# MotorBoardDev.net
KiCad netlist of a schematic drawn in EAGLE
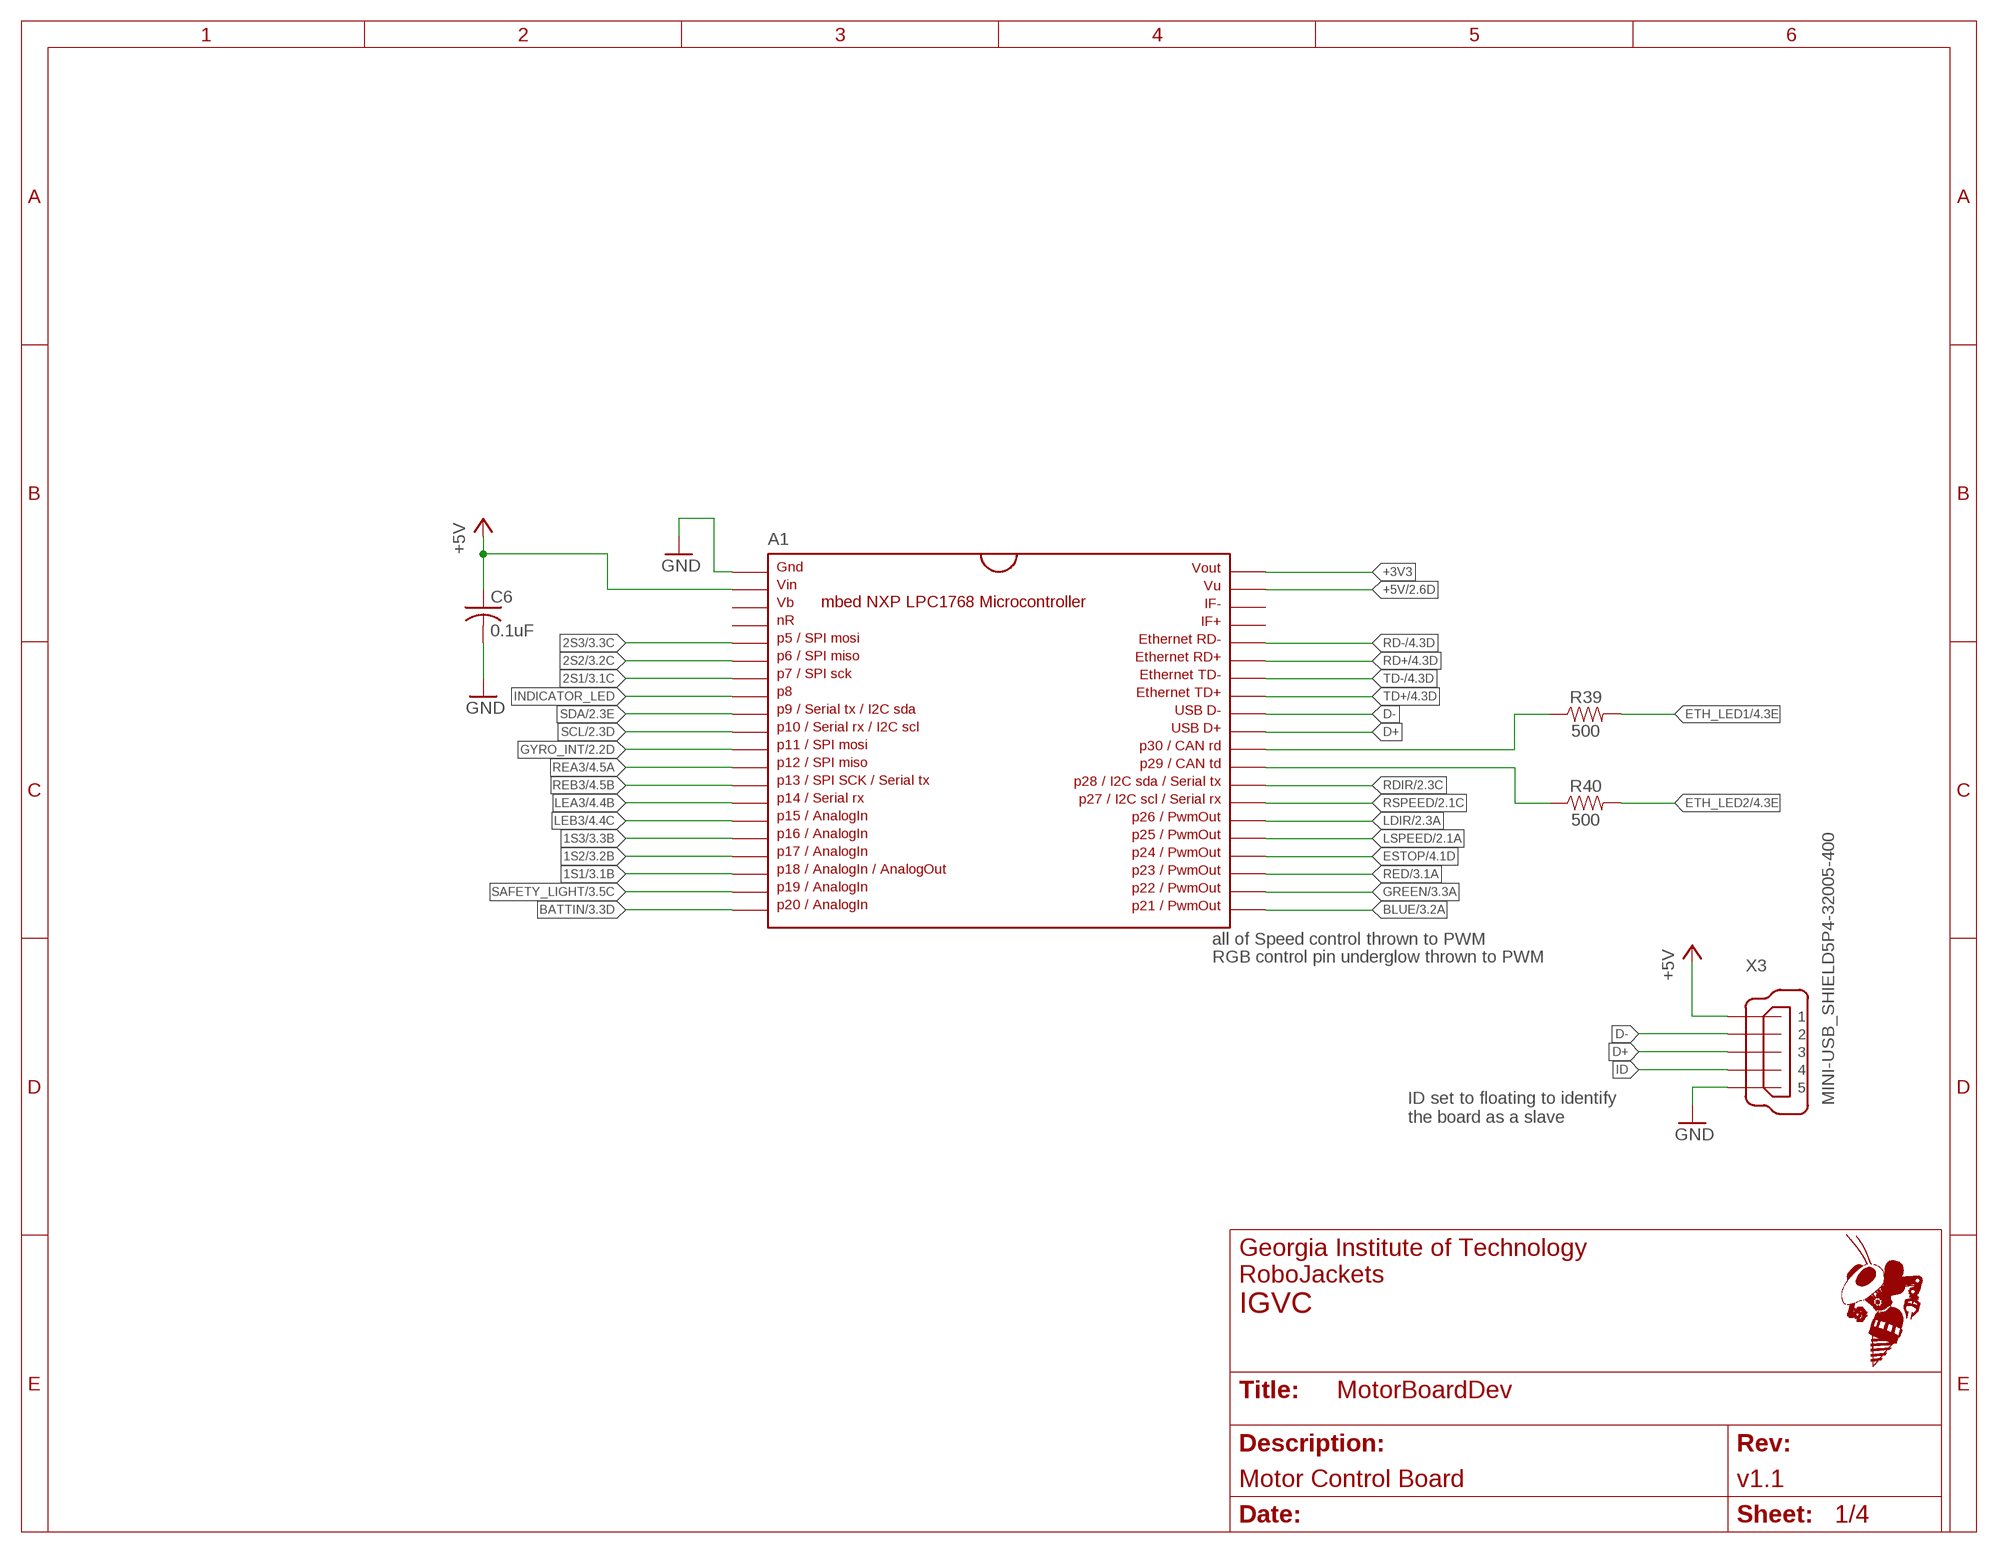
[diagram p0: schematic, sheet 1]
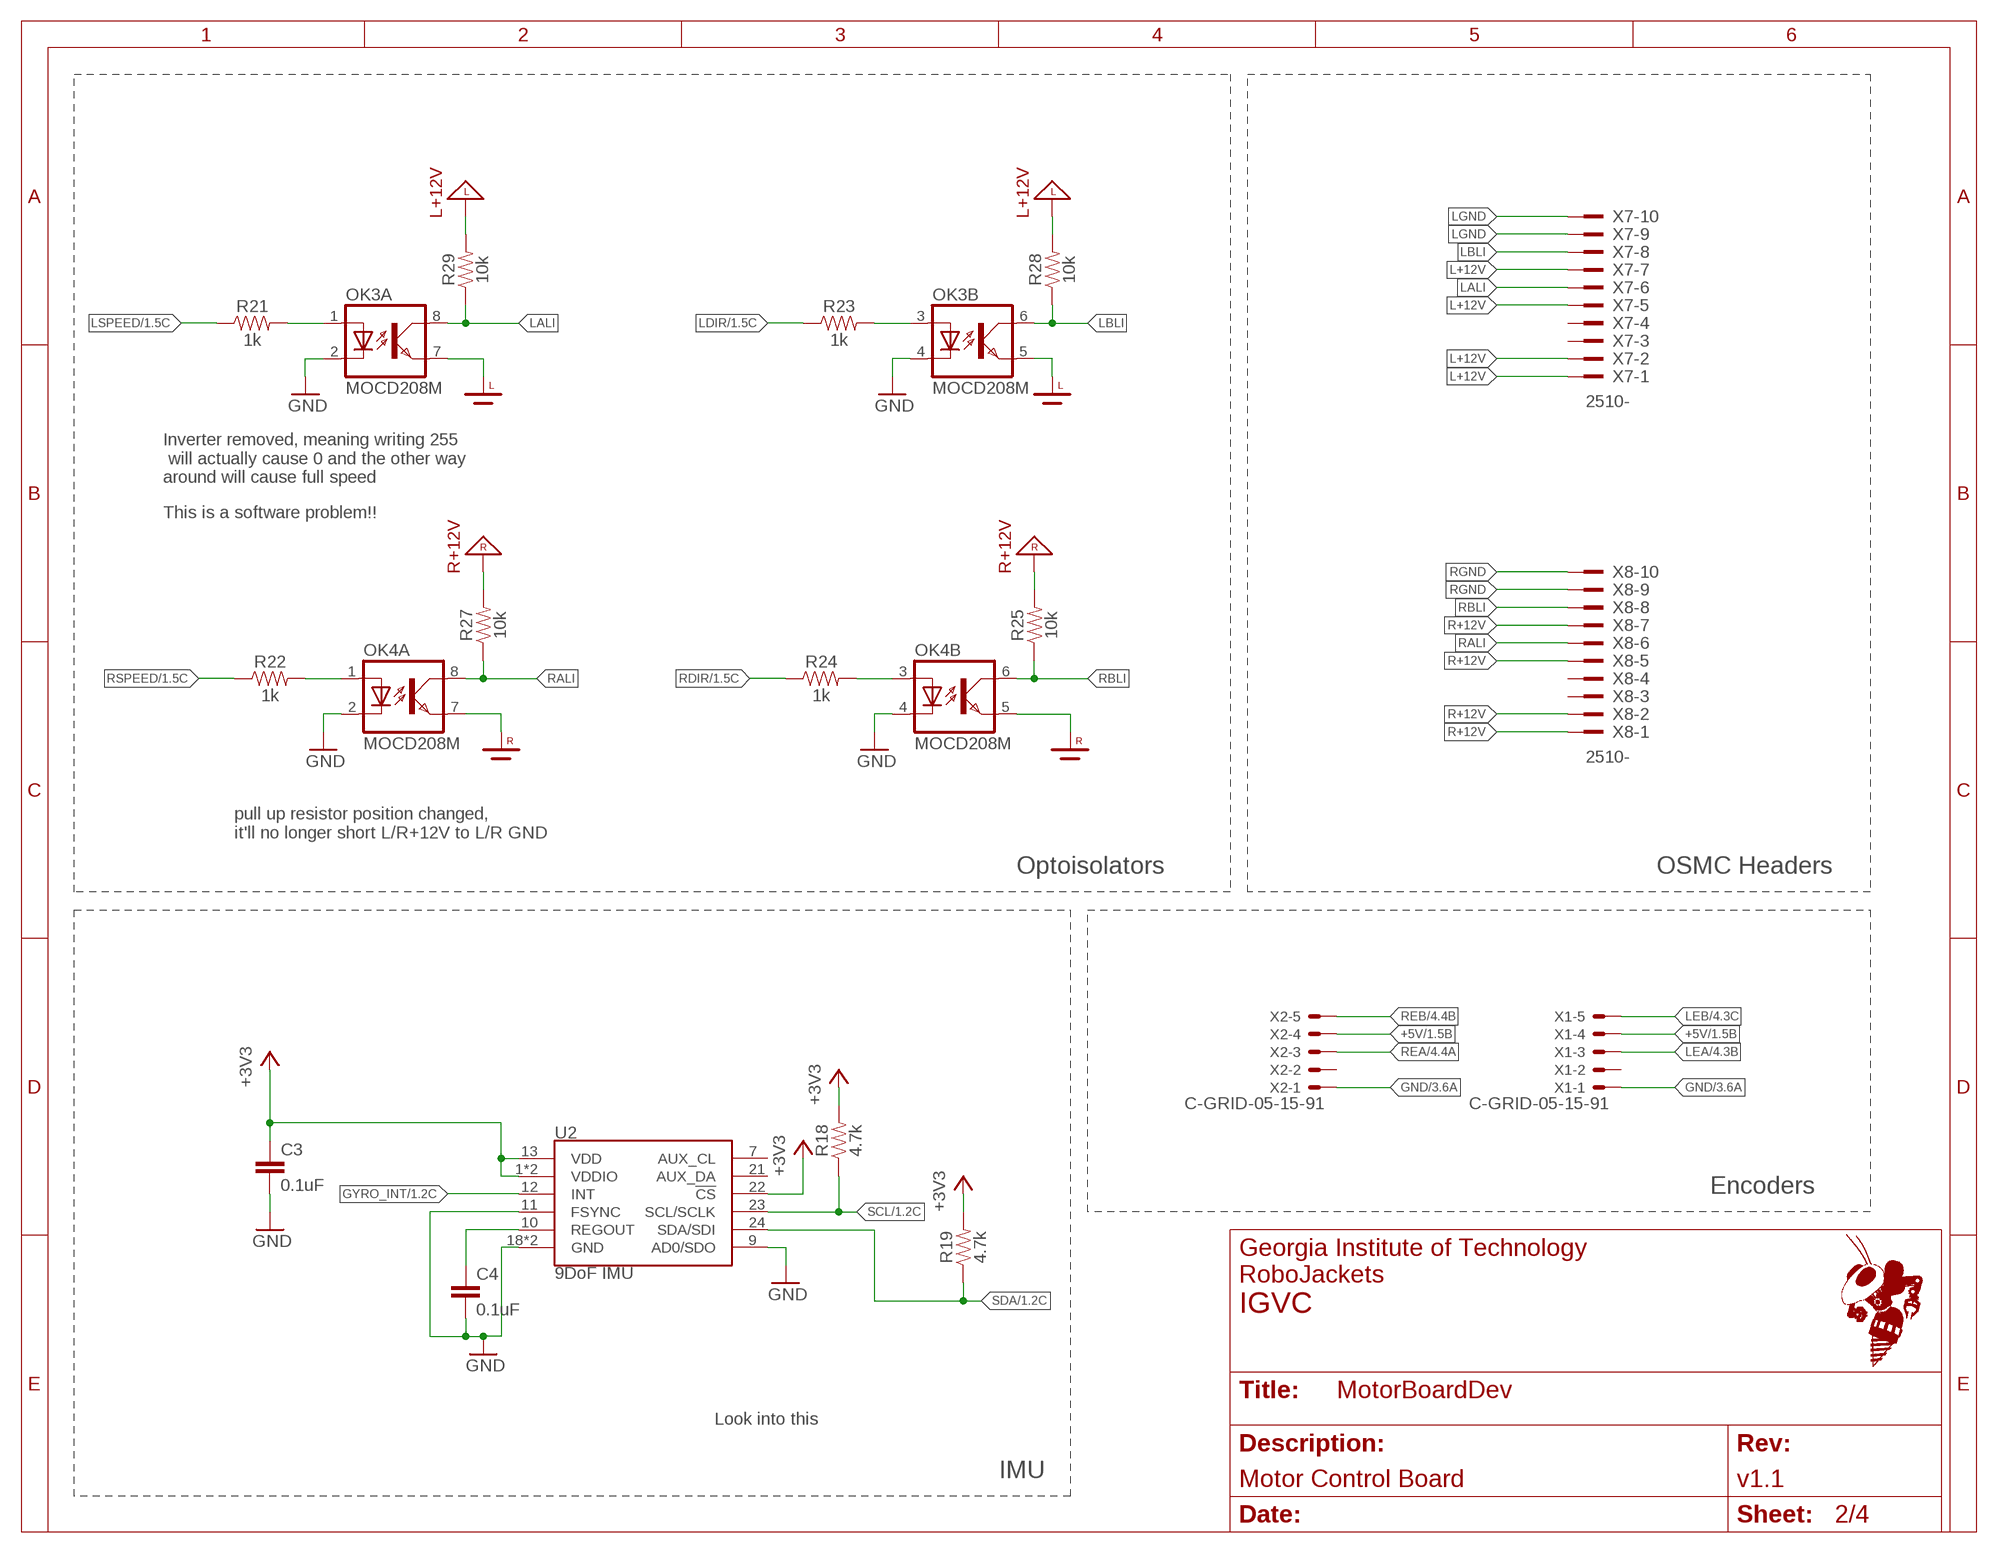
[diagram p1: schematic, sheet 2]
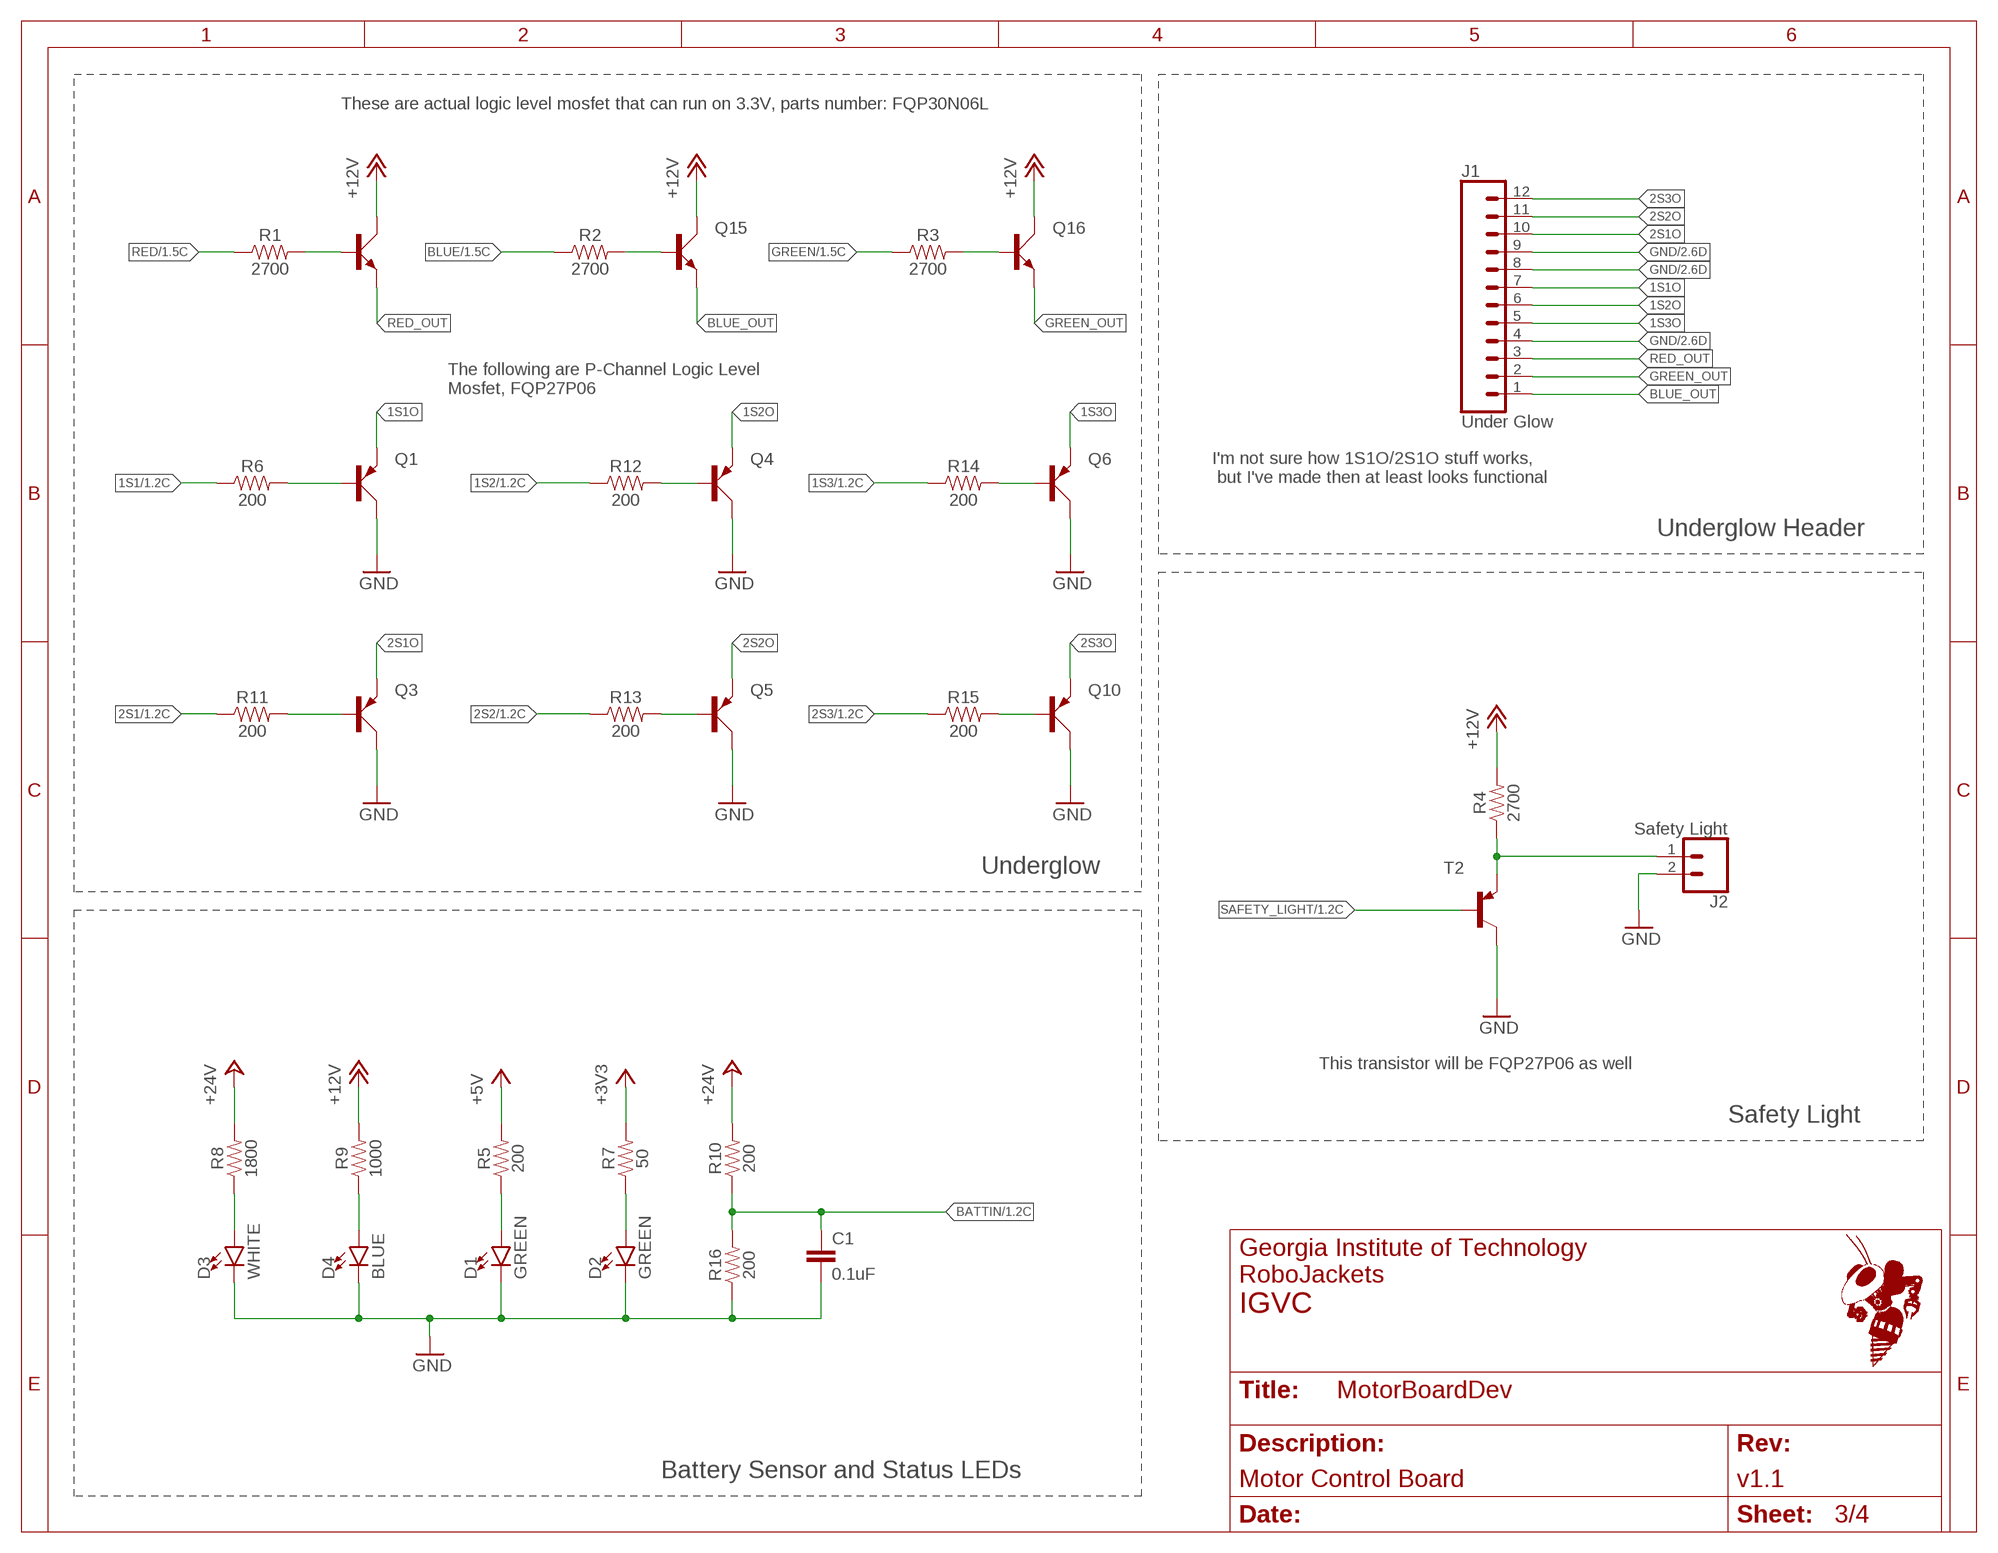
[diagram p2: schematic, sheet 3]
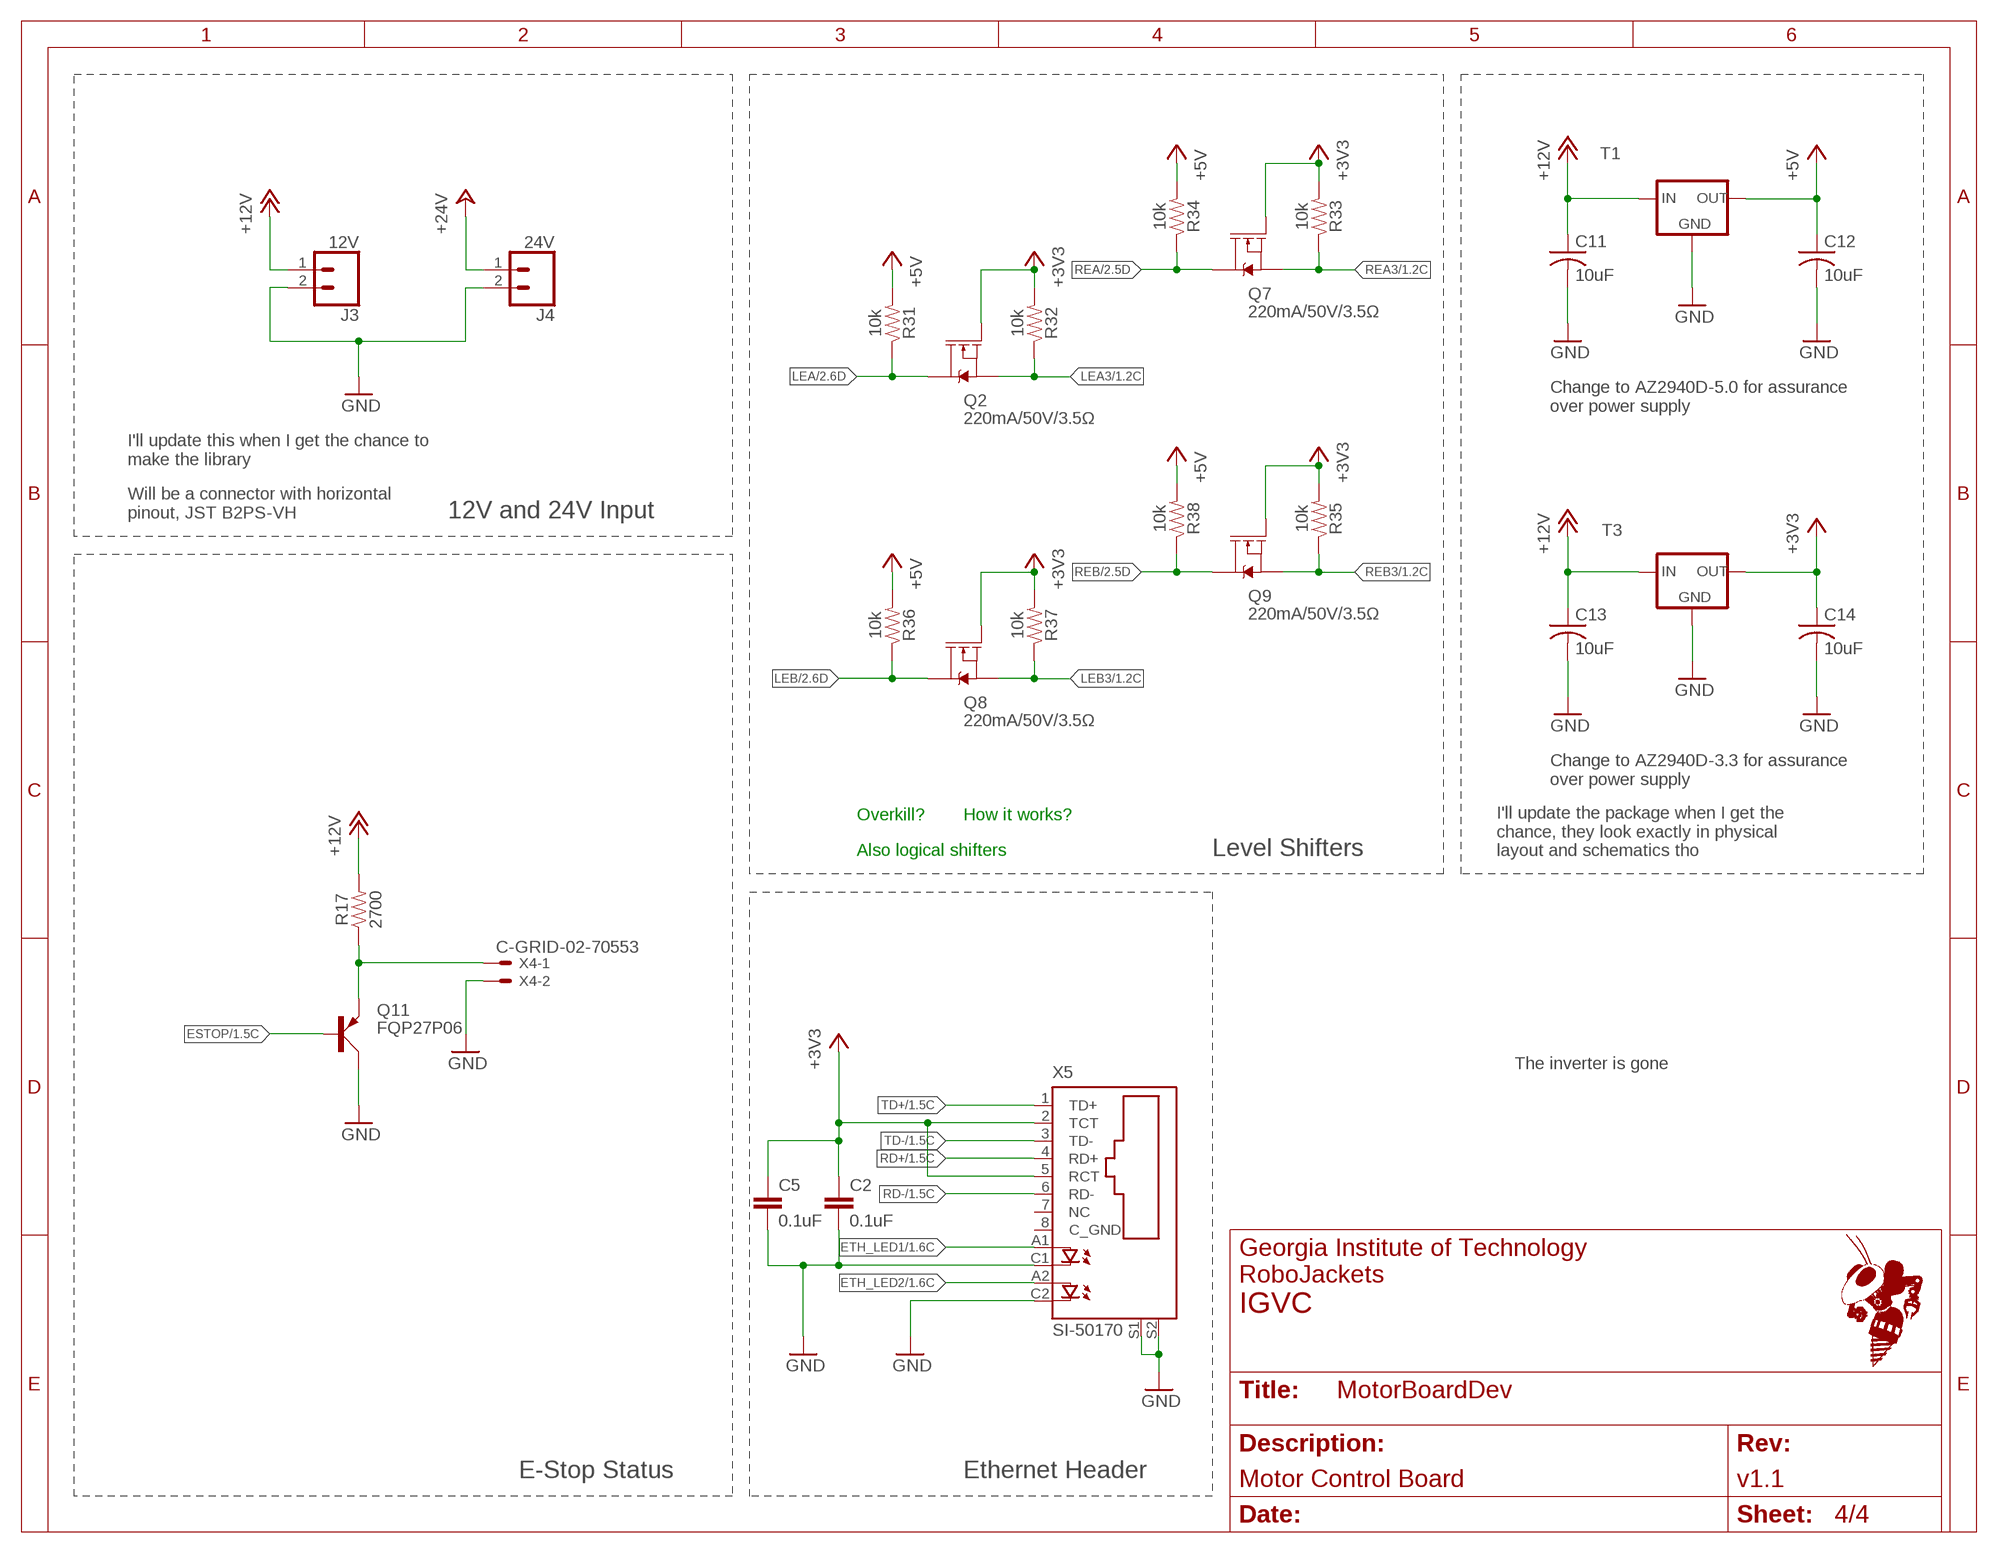
[diagram p3: schematic, sheet 4]

(export (version "E")
  (design (tool "Eeschema 10.0.6"))
  (components
    (comp (ref "C2")
      (value "0.1uF")
      (footprint "eagle-import:0603")
      (libsource (lib "eagle-import") (part "0.1UF-0603-25V-(+80/-20%)"))
    )
    (comp (ref "C5")
      (value "0.1uF")
      (footprint "eagle-import:0603")
      (libsource (lib "eagle-import") (part "0.1UF-0603-25V-(+80/-20%)"))
    )
    (comp (ref "C11")
      (value "10uF")
      (footprint "eagle-import:C0805")
      (libsource (lib "eagle-import") (part "C-USC0805"))
    )
    (comp (ref "C12")
      (value "10uF")
      (footprint "eagle-import:C0805")
      (libsource (lib "eagle-import") (part "C-USC0805"))
    )
    (comp (ref "C13")
      (value "10uF")
      (footprint "eagle-import:C0805")
      (libsource (lib "eagle-import") (part "C-USC0805"))
    )
    (comp (ref "C14")
      (value "10uF")
      (footprint "eagle-import:C0805")
      (libsource (lib "eagle-import") (part "C-USC0805"))
    )
    (comp (ref "J3")
      (value "12V")
      (footprint "eagle-import:SCREWTERMINAL-5MM-2")
      (libsource (lib "eagle-import") (part "CONN_025MM"))
    )
    (comp (ref "J4")
      (value "24V")
      (footprint "eagle-import:SCREWTERMINAL-5MM-2")
      (libsource (lib "eagle-import") (part "CONN_025MM"))
    )
    (comp (ref "Q2")
      (value "220mA/50V/3.5Ω")
      (footprint "eagle-import:SOT23-3")
      (libsource (lib "eagle-import") (part "MOSFET-NCH-BSS138"))
    )
    (comp (ref "Q7")
      (value "220mA/50V/3.5Ω")
      (footprint "eagle-import:SOT23-3")
      (libsource (lib "eagle-import") (part "MOSFET-NCH-BSS138"))
    )
    (comp (ref "Q8")
      (value "220mA/50V/3.5Ω")
      (footprint "eagle-import:SOT23-3")
      (libsource (lib "eagle-import") (part "MOSFET-NCH-BSS138"))
    )
    (comp (ref "Q9")
      (value "220mA/50V/3.5Ω")
      (footprint "eagle-import:SOT23-3")
      (libsource (lib "eagle-import") (part "MOSFET-NCH-BSS138"))
    )
    (comp (ref "Q11")
      (value "TIP42C")
      (footprint "eagle-import:TO220AV")
      (libsource (lib "eagle-import") (part "TIP42C"))
    )
    (comp (ref "R17")
      (value "2700")
      (footprint "eagle-import:0603")
      (libsource (lib "eagle-import") (part "3.9KOHM-0603-1/10W-1%"))
    )
    (comp (ref "R31")
      (value "10k")
      (footprint "eagle-import:0603")
      (libsource (lib "eagle-import") (part "10KOHM-0603-1/10W-1%"))
    )
    (comp (ref "R32")
      (value "10k")
      (footprint "eagle-import:0603")
      (libsource (lib "eagle-import") (part "10KOHM-0603-1/10W-1%"))
    )
    (comp (ref "R33")
      (value "10k")
      (footprint "eagle-import:0603")
      (libsource (lib "eagle-import") (part "10KOHM-0603-1/10W-1%"))
    )
    (comp (ref "R34")
      (value "10k")
      (footprint "eagle-import:0603")
      (libsource (lib "eagle-import") (part "10KOHM-0603-1/10W-1%"))
    )
    (comp (ref "R35")
      (value "10k")
      (footprint "eagle-import:0603")
      (libsource (lib "eagle-import") (part "10KOHM-0603-1/10W-1%"))
    )
    (comp (ref "R36")
      (value "10k")
      (footprint "eagle-import:0603")
      (libsource (lib "eagle-import") (part "10KOHM-0603-1/10W-1%"))
    )
    (comp (ref "R37")
      (value "10k")
      (footprint "eagle-import:0603")
      (libsource (lib "eagle-import") (part "10KOHM-0603-1/10W-1%"))
    )
    (comp (ref "R38")
      (value "10k")
      (footprint "eagle-import:0603")
      (libsource (lib "eagle-import") (part "10KOHM-0603-1/10W-1%"))
    )
    (comp (ref "T1")
      (value "NCP1117DT50GOS-ND")
      (footprint "eagle-import:TO252")
      (libsource (lib "eagle-import") (part "NCP1117DT50GOS-ND"))
    )
    (comp (ref "T3")
      (value "NCP1117DT33GOS-ND")
      (footprint "eagle-import:TO252")
      (libsource (lib "eagle-import") (part "NCP1117DT33GOS-ND"))
    )
    (comp (ref "X4")
      (value "C-GRID-02-70553")
      (footprint "eagle-import:70553-02")
      (libsource (lib "eagle-import") (part "C-GRID-02-70553"))
    )
    (comp (ref "X5")
      (value "SI-50170")
      (footprint "eagle-import:SI-50170")
      (libsource (lib "eagle-import") (part "SI-50170"))
    )
    (comp (ref "A1")
      (value "MBED1768")
      (footprint "eagle-import:SPARKFUN-BOARDS_DIL40_0.9")
      (libsource (lib "eagle-import") (part "SPARKFUN-BOARDS_MBED_NXP_LPC1768"))
    )
    (comp (ref "C6")
      (value "0.1uF")
      (footprint "eagle-import:C0603")
      (libsource (lib "eagle-import") (part "C-USC0603"))
    )
    (comp (ref "R39")
      (value "500")
      (footprint "eagle-import:0603")
      (libsource (lib "eagle-import") (part "1KOHM-0603-1/10W-1%"))
    )
    (comp (ref "R40")
      (value "500")
      (footprint "eagle-import:0603")
      (libsource (lib "eagle-import") (part "1KOHM-0603-1/10W-1%"))
    )
    (comp (ref "X3")
      (value "MINI-USB_SHIELD5P4-32005-400")
      (footprint "eagle-import:32005-400")
      (libsource (lib "eagle-import") (part "MINI-USB_SHIELD5P4-32005-400"))
    )
    (comp (ref "C1")
      (value "0.1uF")
      (footprint "eagle-import:0603")
      (libsource (lib "eagle-import") (part "SparkFun-Capacitors_510_0.1UF-0603-100V-10%"))
    )
    (comp (ref "D1")
      (value "GREEN")
      (footprint "eagle-import:LED-0603")
      (libsource (lib "eagle-import") (part "LED-GREEN0603"))
    )
    (comp (ref "D2")
      (value "GREEN")
      (footprint "eagle-import:LED-0603")
      (libsource (lib "eagle-import") (part "LED-GREEN0603"))
    )
    (comp (ref "D3")
      (value "WHITE")
      (footprint "eagle-import:LED-0603")
      (libsource (lib "eagle-import") (part "LED-WHITE0603"))
    )
    (comp (ref "D4")
      (value "BLUE")
      (footprint "eagle-import:LED-0603")
      (libsource (lib "eagle-import") (part "LED-BLUE0603"))
    )
    (comp (ref "FQP30N06L")
      (value "TIP41C")
      (footprint "eagle-import:TO220AV")
      (libsource (lib "eagle-import") (part "TIP41C"))
    )
    (comp (ref "J1")
      (value "Under Glow")
      (footprint "eagle-import:1X12_LOCK_LONGPADS")
      (libsource (lib "eagle-import") (part "CONN_12LOCK_LONGPADS"))
    )
    (comp (ref "J2")
      (value "Safety Light")
      (footprint "eagle-import:MOLEX-1X2")
      (libsource (lib "eagle-import") (part "SparkFun-Retired_CONN_02POLAR"))
    )
    (comp (ref "Q1")
      (value "TIP42C")
      (footprint "eagle-import:TO220AV")
      (libsource (lib "eagle-import") (part "TIP42C"))
    )
    (comp (ref "Q3")
      (value "TIP42C")
      (footprint "eagle-import:TO220AV")
      (libsource (lib "eagle-import") (part "TIP42C"))
    )
    (comp (ref "Q4")
      (value "TIP42C")
      (footprint "eagle-import:TO220AV")
      (libsource (lib "eagle-import") (part "TIP42C"))
    )
    (comp (ref "Q5")
      (value "TIP42C")
      (footprint "eagle-import:TO220AV")
      (libsource (lib "eagle-import") (part "TIP42C"))
    )
    (comp (ref "Q6")
      (value "TIP42C")
      (footprint "eagle-import:TO220AV")
      (libsource (lib "eagle-import") (part "TIP42C"))
    )
    (comp (ref "Q10")
      (value "TIP42C")
      (footprint "eagle-import:TO220AV")
      (libsource (lib "eagle-import") (part "TIP42C"))
    )
    (comp (ref "Q15")
      (value "TIP41C")
      (footprint "eagle-import:TO220AV")
      (libsource (lib "eagle-import") (part "TIP41C"))
    )
    (comp (ref "Q16")
      (value "TIP41C")
      (footprint "eagle-import:TO220AV")
      (libsource (lib "eagle-import") (part "TIP41C"))
    )
    (comp (ref "R1")
      (value "2700")
      (footprint "eagle-import:0603")
      (libsource (lib "eagle-import") (part "2.55KOHM-0603-1/10W-1%"))
    )
    (comp (ref "R2")
      (value "2700")
      (footprint "eagle-import:0603")
      (libsource (lib "eagle-import") (part "2.55KOHM-0603-1/10W-1%"))
    )
    (comp (ref "R3")
      (value "2700")
      (footprint "eagle-import:0603")
      (libsource (lib "eagle-import") (part "2.55KOHM-0603-1/10W-1%"))
    )
    (comp (ref "R4")
      (value "2700")
      (footprint "eagle-import:0603")
      (libsource (lib "eagle-import") (part "3.9KOHM-0603-1/10W-1%"))
    )
    (comp (ref "R5")
      (value "200")
      (footprint "eagle-import:0603")
      (libsource (lib "eagle-import") (part "200OHM-0603-1/10W-1%"))
    )
    (comp (ref "R6")
      (value "200")
      (footprint "eagle-import:0603")
      (libsource (lib "eagle-import") (part "200OHM-0603-1/10W-1%"))
    )
    (comp (ref "R7")
      (value "50")
      (footprint "eagle-import:0603")
      (libsource (lib "eagle-import") (part "200OHM-0603-1/10W-1%"))
    )
    (comp (ref "R8")
      (value "1800")
      (footprint "eagle-import:0603")
      (libsource (lib "eagle-import") (part "200OHM-0603-1/10W-1%"))
    )
    (comp (ref "R9")
      (value "1000")
      (footprint "eagle-import:0603")
      (libsource (lib "eagle-import") (part "200OHM-0603-1/10W-1%"))
    )
    (comp (ref "R10")
      (value "200")
      (footprint "eagle-import:0603")
      (libsource (lib "eagle-import") (part "200OHM-0603-1/10W-1%"))
    )
    (comp (ref "R11")
      (value "200")
      (footprint "eagle-import:0603")
      (libsource (lib "eagle-import") (part "200OHM-0603-1/10W-1%"))
    )
    (comp (ref "R12")
      (value "200")
      (footprint "eagle-import:0603")
      (libsource (lib "eagle-import") (part "200OHM-0603-1/10W-1%"))
    )
    (comp (ref "R13")
      (value "200")
      (footprint "eagle-import:0603")
      (libsource (lib "eagle-import") (part "200OHM-0603-1/10W-1%"))
    )
    (comp (ref "R14")
      (value "200")
      (footprint "eagle-import:0603")
      (libsource (lib "eagle-import") (part "200OHM-0603-1/10W-1%"))
    )
    (comp (ref "R15")
      (value "200")
      (footprint "eagle-import:0603")
      (libsource (lib "eagle-import") (part "200OHM-0603-1/10W-1%"))
    )
    (comp (ref "R16")
      (value "200")
      (footprint "eagle-import:0603")
      (libsource (lib "eagle-import") (part "200OHM-0603-1/10W-1%"))
    )
    (comp (ref "T2")
      (value "TIP41A")
      (footprint "eagle-import:TO220V")
      (libsource (lib "eagle-import") (part "-PNP-TO220V"))
    )
    (comp (ref "C3")
      (value "0.1uF")
      (footprint "eagle-import:0603")
      (libsource (lib "eagle-import") (part "0.1UF-0603-25V-(+80/-20%)"))
    )
    (comp (ref "C4")
      (value "0.1uF")
      (footprint "eagle-import:0603")
      (libsource (lib "eagle-import") (part "0.1UF-0603-25V-(+80/-20%)"))
    )
    (comp (ref "OK3")
      (value "MOCD208M")
      (footprint "eagle-import:SOIC08-FAIRCHILD")
      (fields (field (name "MF") "FAIRCHILD SEMICONDUCTOR"))
      (libsource (lib "eagle-import") (part "MOCD20M8"))
    )
    (comp (ref "OK4")
      (value "MOCD208M")
      (footprint "eagle-import:SOIC08-FAIRCHILD")
      (fields (field (name "MF") "FAIRCHILD SEMICONDUCTOR"))
      (libsource (lib "eagle-import") (part "MOCD20M8"))
    )
    (comp (ref "R18")
      (value "4.7k")
      (footprint "eagle-import:0603")
      (libsource (lib "eagle-import") (part "4.7KOHM-0603-1/10W-1%"))
    )
    (comp (ref "R19")
      (value "4.7k")
      (footprint "eagle-import:0603")
      (libsource (lib "eagle-import") (part "4.7KOHM-0603-1/10W-1%"))
    )
    (comp (ref "R21")
      (value "1k")
      (footprint "eagle-import:0603")
      (libsource (lib "eagle-import") (part "1KOHM-0603-1/10W-1%"))
    )
    (comp (ref "R22")
      (value "1k")
      (footprint "eagle-import:0603")
      (libsource (lib "eagle-import") (part "1KOHM-0603-1/10W-1%"))
    )
    (comp (ref "R23")
      (value "1k")
      (footprint "eagle-import:0603")
      (libsource (lib "eagle-import") (part "1KOHM-0603-1/10W-1%"))
    )
    (comp (ref "R24")
      (value "1k")
      (footprint "eagle-import:0603")
      (libsource (lib "eagle-import") (part "1KOHM-0603-1/10W-1%"))
    )
    (comp (ref "R25")
      (value "10k")
      (footprint "eagle-import:0603")
      (libsource (lib "eagle-import") (part "10KOHM-0603-1/10W-1%"))
    )
    (comp (ref "R27")
      (value "10k")
      (footprint "eagle-import:0603")
      (libsource (lib "eagle-import") (part "10KOHM-0603-1/10W-1%"))
    )
    (comp (ref "R28")
      (value "10k")
      (footprint "eagle-import:0603")
      (libsource (lib "eagle-import") (part "10KOHM-0603-1/10W-1%"))
    )
    (comp (ref "R29")
      (value "10k")
      (footprint "eagle-import:0603")
      (libsource (lib "eagle-import") (part "10KOHM-0603-1/10W-1%"))
    )
    (comp (ref "U2")
      (value "9DoF IMU")
      (footprint "eagle-import:QFN24-3X3")
      (libsource (lib "eagle-import") (part "MPU-9250"))
    )
    (comp (ref "X1")
      (value "C-GRID-05-15-91")
      (footprint "eagle-import:15-91-05")
      (libsource (lib "eagle-import") (part "C-GRID-05-15-91"))
    )
    (comp (ref "X2")
      (value "C-GRID-05-15-91")
      (footprint "eagle-import:15-91-05")
      (libsource (lib "eagle-import") (part "C-GRID-05-15-91"))
    )
    (comp (ref "X7")
      (value "2510-")
      (footprint "eagle-import:PAK100_2500-10")
      (fields (field (name "MF") "3M") (field (name "MPN") "2510-6002UB"))
      (libsource (lib "eagle-import") (part "2510-"))
    )
    (comp (ref "X8")
      (value "2510-")
      (footprint "eagle-import:PAK100_2500-10")
      (fields (field (name "MF") "3M") (field (name "MPN") "2510-6002UB"))
      (libsource (lib "eagle-import") (part "2510-"))
    )
  )
  (nets
    (net (code "1") (name "+3V3") (class "Default")
      (node (ref "A1") (pin "40") (pinfunction "P$40_40") (pintype "bidirectional"))
      (node (ref "C14") (pin "1") (pinfunction "1_1") (pintype "passive"))
      (node (ref "C2") (pin "1") (pinfunction "1_1") (pintype "passive"))
      (node (ref "C3") (pin "1") (pinfunction "1_1") (pintype "passive"))
      (node (ref "C5") (pin "1") (pinfunction "1_1") (pintype "passive"))
      (node (ref "Q2") (pin "1") (pinfunction "G_1") (pintype "bidirectional"))
      (node (ref "Q7") (pin "1") (pinfunction "G_1") (pintype "bidirectional"))
      (node (ref "Q8") (pin "1") (pinfunction "G_1") (pintype "bidirectional"))
      (node (ref "Q9") (pin "1") (pinfunction "G_1") (pintype "bidirectional"))
      (node (ref "R18") (pin "2") (pinfunction "2_2") (pintype "passive"))
      (node (ref "R19") (pin "2") (pinfunction "2_2") (pintype "passive"))
      (node (ref "R32") (pin "2") (pinfunction "2_2") (pintype "passive"))
      (node (ref "R33") (pin "2") (pinfunction "2_2") (pintype "passive"))
      (node (ref "R35") (pin "2") (pinfunction "2_2") (pintype "passive"))
      (node (ref "R37") (pin "2") (pinfunction "2_2") (pintype "passive"))
      (node (ref "R7") (pin "2") (pinfunction "2_2") (pintype "passive"))
      (node (ref "T3") (pin "2") (pinfunction "OUT_2") (pintype "passive"))
      (node (ref "U2") (pin "1") (pinfunction "VDDIO_1") (pintype "bidirectional"))
      (node (ref "U2") (pin "13") (pinfunction "VDD_13") (pintype "bidirectional"))
      (node (ref "U2") (pin "22") (pinfunction "~{CS}_22") (pintype "bidirectional"))
      (node (ref "U2") (pin "8") (pinfunction "VDDIO_8") (pintype "bidirectional"))
      (node (ref "X5") (pin "2") (pinfunction "TCT_2") (pintype "passive"))
      (node (ref "X5") (pin "5") (pinfunction "RCT_5") (pintype "passive"))
    )
    (net (code "2") (name "+5V") (class "Default")
      (node (ref "A1") (pin "2") (pinfunction "P$2_2") (pintype "bidirectional"))
      (node (ref "A1") (pin "39") (pinfunction "P$39_39") (pintype "bidirectional"))
      (node (ref "C12") (pin "1") (pinfunction "1_1") (pintype "passive"))
      (node (ref "C6") (pin "1") (pinfunction "1_1") (pintype "passive"))
      (node (ref "R31") (pin "2") (pinfunction "2_2") (pintype "passive"))
      (node (ref "R34") (pin "2") (pinfunction "2_2") (pintype "passive"))
      (node (ref "R36") (pin "2") (pinfunction "2_2") (pintype "passive"))
      (node (ref "R38") (pin "2") (pinfunction "2_2") (pintype "passive"))
      (node (ref "R5") (pin "2") (pinfunction "2_2") (pintype "passive"))
      (node (ref "T1") (pin "2") (pinfunction "OUT_2") (pintype "passive"))
      (node (ref "X1") (pin "4") (pinfunction "S_4") (pintype "passive"))
      (node (ref "X2") (pin "4") (pinfunction "S_4") (pintype "passive"))
      (node (ref "X3") (pin "1") (pinfunction "1_1") (pintype "passive"))
    )
    (net (code "3") (name "+12V") (class "Default")
      (node (ref "C11") (pin "1") (pinfunction "1_1") (pintype "passive"))
      (node (ref "C13") (pin "1") (pinfunction "1_1") (pintype "passive"))
      (node (ref "FQP30N06L") (pin "C") (pinfunction "C_C") (pintype "passive"))
      (node (ref "J3") (pin "1") (pinfunction "1_1") (pintype "passive"))
      (node (ref "Q15") (pin "C") (pinfunction "C_C") (pintype "passive"))
      (node (ref "Q16") (pin "C") (pinfunction "C_C") (pintype "passive"))
      (node (ref "R17") (pin "2") (pinfunction "2_2") (pintype "passive"))
      (node (ref "R4") (pin "2") (pinfunction "2_2") (pintype "passive"))
      (node (ref "R9") (pin "2") (pinfunction "2_2") (pintype "passive"))
      (node (ref "T1") (pin "3") (pinfunction "IN_3") (pintype "input"))
      (node (ref "T3") (pin "3") (pinfunction "IN_3") (pintype "input"))
    )
    (net (code "4") (name "+24V") (class "Default")
      (node (ref "J4") (pin "1") (pinfunction "1_1") (pintype "passive"))
      (node (ref "R10") (pin "2") (pinfunction "2_2") (pintype "passive"))
      (node (ref "R8") (pin "2") (pinfunction "2_2") (pintype "passive"))
    )
    (net (code "5") (name "1S1") (class "Default")
      (node (ref "A1") (pin "18") (pinfunction "P$18_18") (pintype "bidirectional"))
      (node (ref "R6") (pin "1") (pinfunction "1_1") (pintype "passive"))
    )
    (net (code "6") (name "1S1O") (class "Default")
      (node (ref "J1") (pin "7") (pinfunction "7_7") (pintype "passive"))
      (node (ref "Q1") (pin "E") (pinfunction "E_E") (pintype "passive"))
    )
    (net (code "7") (name "1S2") (class "Default")
      (node (ref "A1") (pin "17") (pinfunction "P$17_17") (pintype "bidirectional"))
      (node (ref "R12") (pin "1") (pinfunction "1_1") (pintype "passive"))
    )
    (net (code "8") (name "1S2O") (class "Default")
      (node (ref "J1") (pin "6") (pinfunction "6_6") (pintype "passive"))
      (node (ref "Q4") (pin "E") (pinfunction "E_E") (pintype "passive"))
    )
    (net (code "9") (name "1S3") (class "Default")
      (node (ref "A1") (pin "16") (pinfunction "P$16_16") (pintype "bidirectional"))
      (node (ref "R14") (pin "1") (pinfunction "1_1") (pintype "passive"))
    )
    (net (code "10") (name "1S3O") (class "Default")
      (node (ref "J1") (pin "5") (pinfunction "5_5") (pintype "passive"))
      (node (ref "Q6") (pin "E") (pinfunction "E_E") (pintype "passive"))
    )
    (net (code "11") (name "2S1") (class "Default")
      (node (ref "A1") (pin "7") (pinfunction "P$7_7") (pintype "bidirectional"))
      (node (ref "R11") (pin "1") (pinfunction "1_1") (pintype "passive"))
    )
    (net (code "12") (name "2S1O") (class "Default")
      (node (ref "J1") (pin "10") (pinfunction "10_10") (pintype "passive"))
      (node (ref "Q3") (pin "E") (pinfunction "E_E") (pintype "passive"))
    )
    (net (code "13") (name "2S2") (class "Default")
      (node (ref "A1") (pin "6") (pinfunction "P$6_6") (pintype "bidirectional"))
      (node (ref "R13") (pin "1") (pinfunction "1_1") (pintype "passive"))
    )
    (net (code "14") (name "2S2O") (class "Default")
      (node (ref "J1") (pin "11") (pinfunction "11_11") (pintype "passive"))
      (node (ref "Q5") (pin "E") (pinfunction "E_E") (pintype "passive"))
    )
    (net (code "15") (name "2S3") (class "Default")
      (node (ref "A1") (pin "5") (pinfunction "P$5_5") (pintype "bidirectional"))
      (node (ref "R15") (pin "1") (pinfunction "1_1") (pintype "passive"))
    )
    (net (code "16") (name "2S3O") (class "Default")
      (node (ref "J1") (pin "12") (pinfunction "12_12") (pintype "passive"))
      (node (ref "Q10") (pin "E") (pinfunction "E_E") (pintype "passive"))
    )
    (net (code "17") (name "BATTIN") (class "Default")
      (node (ref "A1") (pin "20") (pinfunction "P$20_20") (pintype "bidirectional"))
      (node (ref "C1") (pin "1") (pinfunction "1_1") (pintype "passive"))
      (node (ref "R10") (pin "1") (pinfunction "1_1") (pintype "passive"))
      (node (ref "R16") (pin "2") (pinfunction "2_2") (pintype "passive"))
    )
    (net (code "18") (name "BLUE") (class "Default")
      (node (ref "A1") (pin "21") (pinfunction "P$21_21") (pintype "bidirectional"))
      (node (ref "R2") (pin "1") (pinfunction "1_1") (pintype "passive"))
    )
    (net (code "19") (name "BLUE_OUT") (class "Default")
      (node (ref "J1") (pin "1") (pinfunction "1_1") (pintype "passive"))
      (node (ref "Q15") (pin "E") (pinfunction "E_E") (pintype "passive"))
    )
    (net (code "20") (name "D+") (class "Default")
      (node (ref "A1") (pin "31") (pinfunction "P$31_31") (pintype "bidirectional"))
      (node (ref "X3") (pin "3") (pinfunction "3_3") (pintype "passive"))
    )
    (net (code "21") (name "D-") (class "Default")
      (node (ref "A1") (pin "32") (pinfunction "P$32_32") (pintype "bidirectional"))
      (node (ref "X3") (pin "2") (pinfunction "2_2") (pintype "passive"))
    )
    (net (code "22") (name "ESTOP") (class "Default")
      (node (ref "A1") (pin "24") (pinfunction "P$24_24") (pintype "bidirectional"))
      (node (ref "Q11") (pin "B") (pinfunction "B_B") (pintype "passive"))
    )
    (net (code "23") (name "ETH_LED1") (class "Default")
      (node (ref "R39") (pin "2") (pinfunction "2_2") (pintype "passive"))
      (node (ref "X5") (pin "A1") (pinfunction "A_A1") (pintype "passive"))
    )
    (net (code "24") (name "ETH_LED2") (class "Default")
      (node (ref "R40") (pin "2") (pinfunction "2_2") (pintype "passive"))
      (node (ref "X5") (pin "A2") (pinfunction "A1_A2") (pintype "passive"))
    )
    (net (code "25") (name "GND") (class "Default")
      (node (ref "A1") (pin "1") (pinfunction "P$1_1") (pintype "bidirectional"))
      (node (ref "C1") (pin "2") (pinfunction "2_2") (pintype "passive"))
      (node (ref "C11") (pin "2") (pinfunction "2_2") (pintype "passive"))
      (node (ref "C12") (pin "2") (pinfunction "2_2") (pintype "passive"))
      (node (ref "C13") (pin "2") (pinfunction "2_2") (pintype "passive"))
      (node (ref "C14") (pin "2") (pinfunction "2_2") (pintype "passive"))
      (node (ref "C2") (pin "2") (pinfunction "2_2") (pintype "passive"))
      (node (ref "C3") (pin "2") (pinfunction "2_2") (pintype "passive"))
      (node (ref "C4") (pin "2") (pinfunction "2_2") (pintype "passive"))
      (node (ref "C5") (pin "2") (pinfunction "2_2") (pintype "passive"))
      (node (ref "C6") (pin "2") (pinfunction "2_2") (pintype "passive"))
      (node (ref "D1") (pin "C") (pinfunction "C_C") (pintype "passive"))
      (node (ref "D2") (pin "C") (pinfunction "C_C") (pintype "passive"))
      (node (ref "D3") (pin "C") (pinfunction "C_C") (pintype "passive"))
      (node (ref "D4") (pin "C") (pinfunction "C_C") (pintype "passive"))
      (node (ref "J1") (pin "4") (pinfunction "4_4") (pintype "passive"))
      (node (ref "J1") (pin "8") (pinfunction "8_8") (pintype "passive"))
      (node (ref "J1") (pin "9") (pinfunction "9_9") (pintype "passive"))
      (node (ref "J2") (pin "2") (pinfunction "2_2") (pintype "passive"))
      (node (ref "J3") (pin "2") (pinfunction "2_2") (pintype "passive"))
      (node (ref "J4") (pin "2") (pinfunction "2_2") (pintype "passive"))
      (node (ref "OK3") (pin "2") (pinfunction "C_2") (pintype "passive"))
      (node (ref "OK3") (pin "4") (pinfunction "C_4") (pintype "passive"))
      (node (ref "OK4") (pin "2") (pinfunction "C_2") (pintype "passive"))
      (node (ref "OK4") (pin "4") (pinfunction "C_4") (pintype "passive"))
      (node (ref "Q1") (pin "C") (pinfunction "C_C") (pintype "passive"))
      (node (ref "Q10") (pin "C") (pinfunction "C_C") (pintype "passive"))
      (node (ref "Q11") (pin "C") (pinfunction "C_C") (pintype "passive"))
      (node (ref "Q3") (pin "C") (pinfunction "C_C") (pintype "passive"))
      (node (ref "Q4") (pin "C") (pinfunction "C_C") (pintype "passive"))
      (node (ref "Q5") (pin "C") (pinfunction "C_C") (pintype "passive"))
      (node (ref "Q6") (pin "C") (pinfunction "C_C") (pintype "passive"))
      (node (ref "R16") (pin "1") (pinfunction "1_1") (pintype "passive"))
      (node (ref "T1") (pin "1") (pinfunction "GND_1") (pintype "input"))
      (node (ref "T2") (pin "2") (pinfunction "C_2") (pintype "passive"))
      (node (ref "T3") (pin "1") (pinfunction "GND_1") (pintype "input"))
      (node (ref "U2") (pin "11") (pinfunction "FSYNC_11") (pintype "bidirectional"))
      (node (ref "U2") (pin "18") (pinfunction "GND_18") (pintype "bidirectional"))
      (node (ref "U2") (pin "20") (pinfunction "GND_20") (pintype "bidirectional"))
      (node (ref "U2") (pin "9") (pinfunction "AD0/SDO_9") (pintype "bidirectional"))
      (node (ref "X1") (pin "1") (pinfunction "S_1") (pintype "passive"))
      (node (ref "X2") (pin "1") (pinfunction "S_1") (pintype "passive"))
      (node (ref "X3") (pin "5") (pinfunction "5_5") (pintype "passive"))
      (node (ref "X4") (pin "2") (pinfunction "S_2") (pintype "passive"))
      (node (ref "X5") (pin "C1") (pinfunction "C_C1") (pintype "passive"))
      (node (ref "X5") (pin "C2") (pinfunction "C1_C2") (pintype "passive"))
      (node (ref "X5") (pin "S1") (pinfunction "S1_S1") (pintype "passive"))
      (node (ref "X5") (pin "S2") (pinfunction "S2_S2") (pintype "passive"))
    )
    (net (code "26") (name "GREEN") (class "Default")
      (node (ref "A1") (pin "22") (pinfunction "P$22_22") (pintype "bidirectional"))
      (node (ref "R3") (pin "1") (pinfunction "1_1") (pintype "passive"))
    )
    (net (code "27") (name "GREEN_OUT") (class "Default")
      (node (ref "J1") (pin "2") (pinfunction "2_2") (pintype "passive"))
      (node (ref "Q16") (pin "E") (pinfunction "E_E") (pintype "passive"))
    )
    (net (code "28") (name "GYRO_INT") (class "Default")
      (node (ref "A1") (pin "11") (pinfunction "P$11_11") (pintype "bidirectional"))
      (node (ref "U2") (pin "12") (pinfunction "INT_12") (pintype "bidirectional"))
    )
    (net (code "29") (name "ID") (class "Default")
      (node (ref "X3") (pin "4") (pinfunction "4_4") (pintype "passive"))
    )
    (net (code "30") (name "INDICATOR_LED") (class "Default")
      (node (ref "A1") (pin "8") (pinfunction "P$8_8") (pintype "bidirectional"))
    )
    (net (code "31") (name "L+12V") (class "Default")
      (node (ref "R28") (pin "2") (pinfunction "2_2") (pintype "passive"))
      (node (ref "R29") (pin "2") (pinfunction "2_2") (pintype "passive"))
      (node (ref "X7") (pin "1") (pinfunction "KL_1") (pintype "passive"))
      (node (ref "X7") (pin "2") (pinfunction "KL_2") (pintype "passive"))
      (node (ref "X7") (pin "5") (pinfunction "KL_5") (pintype "passive"))
      (node (ref "X7") (pin "7") (pinfunction "KL_7") (pintype "passive"))
    )
    (net (code "32") (name "LALI") (class "Default")
      (node (ref "OK3") (pin "8") (pinfunction "COL_8") (pintype "passive"))
      (node (ref "R29") (pin "1") (pinfunction "1_1") (pintype "passive"))
      (node (ref "X7") (pin "6") (pinfunction "KL_6") (pintype "passive"))
    )
    (net (code "33") (name "LBLI") (class "Default")
      (node (ref "OK3") (pin "6") (pinfunction "COL_6") (pintype "passive"))
      (node (ref "R28") (pin "1") (pinfunction "1_1") (pintype "passive"))
      (node (ref "X7") (pin "8") (pinfunction "KL_8") (pintype "passive"))
    )
    (net (code "34") (name "LDIR") (class "Default")
      (node (ref "A1") (pin "26") (pinfunction "P$26_26") (pintype "bidirectional"))
      (node (ref "R23") (pin "1") (pinfunction "1_1") (pintype "passive"))
    )
    (net (code "35") (name "LEA") (class "Default")
      (node (ref "Q2") (pin "3") (pinfunction "D_3") (pintype "bidirectional"))
      (node (ref "R31") (pin "1") (pinfunction "1_1") (pintype "passive"))
      (node (ref "X1") (pin "3") (pinfunction "S_3") (pintype "passive"))
    )
    (net (code "36") (name "LEA3") (class "Default")
      (node (ref "A1") (pin "14") (pinfunction "P$14_14") (pintype "bidirectional"))
      (node (ref "Q2") (pin "2") (pinfunction "S_2") (pintype "bidirectional"))
      (node (ref "R32") (pin "1") (pinfunction "1_1") (pintype "passive"))
    )
    (net (code "37") (name "LEB") (class "Default")
      (node (ref "Q8") (pin "3") (pinfunction "D_3") (pintype "bidirectional"))
      (node (ref "R36") (pin "1") (pinfunction "1_1") (pintype "passive"))
      (node (ref "X1") (pin "5") (pinfunction "S_5") (pintype "passive"))
    )
    (net (code "38") (name "LEB3") (class "Default")
      (node (ref "A1") (pin "15") (pinfunction "P$15_15") (pintype "bidirectional"))
      (node (ref "Q8") (pin "2") (pinfunction "S_2") (pintype "bidirectional"))
      (node (ref "R37") (pin "1") (pinfunction "1_1") (pintype "passive"))
    )
    (net (code "39") (name "LGND") (class "Default")
      (node (ref "OK3") (pin "5") (pinfunction "EMIT_5") (pintype "passive"))
      (node (ref "OK3") (pin "7") (pinfunction "EMIT_7") (pintype "passive"))
      (node (ref "X7") (pin "10") (pinfunction "KL_10") (pintype "passive"))
      (node (ref "X7") (pin "9") (pinfunction "KL_9") (pintype "passive"))
    )
    (net (code "40") (name "LSPEED") (class "Default")
      (node (ref "A1") (pin "25") (pinfunction "P$25_25") (pintype "bidirectional"))
      (node (ref "R21") (pin "1") (pinfunction "1_1") (pintype "passive"))
    )
    (net (code "41") (name "Net-(A1-P$29)") (class "Default")
      (node (ref "A1") (pin "29") (pinfunction "P$29_29") (pintype "bidirectional"))
      (node (ref "R40") (pin "1") (pinfunction "1_1") (pintype "passive"))
    )
    (net (code "42") (name "Net-(A1-P$30)") (class "Default")
      (node (ref "A1") (pin "30") (pinfunction "P$30_30") (pintype "bidirectional"))
      (node (ref "R39") (pin "1") (pinfunction "1_1") (pintype "passive"))
    )
    (net (code "43") (name "Net-(D1-PadA)") (class "Default")
      (node (ref "D1") (pin "A") (pinfunction "A_A") (pintype "passive"))
      (node (ref "R5") (pin "1") (pinfunction "1_1") (pintype "passive"))
    )
    (net (code "44") (name "Net-(D2-PadA)") (class "Default")
      (node (ref "D2") (pin "A") (pinfunction "A_A") (pintype "passive"))
      (node (ref "R7") (pin "1") (pinfunction "1_1") (pintype "passive"))
    )
    (net (code "45") (name "Net-(D3-PadA)") (class "Default")
      (node (ref "D3") (pin "A") (pinfunction "A_A") (pintype "passive"))
      (node (ref "R8") (pin "1") (pinfunction "1_1") (pintype "passive"))
    )
    (net (code "46") (name "Net-(D4-PadA)") (class "Default")
      (node (ref "D4") (pin "A") (pinfunction "A_A") (pintype "passive"))
      (node (ref "R9") (pin "1") (pinfunction "1_1") (pintype "passive"))
    )
    (net (code "47") (name "Net-(FQP30N06L-PadB)") (class "Default")
      (node (ref "FQP30N06L") (pin "B") (pinfunction "B_B") (pintype "passive"))
      (node (ref "R1") (pin "2") (pinfunction "2_2") (pintype "passive"))
    )
    (net (code "48") (name "Net-(OK3A-A)") (class "Default")
      (node (ref "OK3") (pin "1") (pinfunction "A_1") (pintype "passive"))
      (node (ref "R21") (pin "2") (pinfunction "2_2") (pintype "passive"))
    )
    (net (code "49") (name "Net-(OK3B-A)") (class "Default")
      (node (ref "OK3") (pin "3") (pinfunction "A_3") (pintype "passive"))
      (node (ref "R23") (pin "2") (pinfunction "2_2") (pintype "passive"))
    )
    (net (code "50") (name "Net-(OK4A-A)") (class "Default")
      (node (ref "OK4") (pin "1") (pinfunction "A_1") (pintype "passive"))
      (node (ref "R22") (pin "2") (pinfunction "2_2") (pintype "passive"))
    )
    (net (code "51") (name "Net-(OK4B-A)") (class "Default")
      (node (ref "OK4") (pin "3") (pinfunction "A_3") (pintype "passive"))
      (node (ref "R24") (pin "2") (pinfunction "2_2") (pintype "passive"))
    )
    (net (code "52") (name "Net-(Q1-PadB)") (class "Default")
      (node (ref "Q1") (pin "B") (pinfunction "B_B") (pintype "passive"))
      (node (ref "R6") (pin "2") (pinfunction "2_2") (pintype "passive"))
    )
    (net (code "53") (name "Net-(Q3-PadB)") (class "Default")
      (node (ref "Q3") (pin "B") (pinfunction "B_B") (pintype "passive"))
      (node (ref "R11") (pin "2") (pinfunction "2_2") (pintype "passive"))
    )
    (net (code "54") (name "Net-(Q4-PadB)") (class "Default")
      (node (ref "Q4") (pin "B") (pinfunction "B_B") (pintype "passive"))
      (node (ref "R12") (pin "2") (pinfunction "2_2") (pintype "passive"))
    )
    (net (code "55") (name "Net-(Q5-PadB)") (class "Default")
      (node (ref "Q5") (pin "B") (pinfunction "B_B") (pintype "passive"))
      (node (ref "R13") (pin "2") (pinfunction "2_2") (pintype "passive"))
    )
    (net (code "56") (name "Net-(Q6-PadB)") (class "Default")
      (node (ref "Q6") (pin "B") (pinfunction "B_B") (pintype "passive"))
      (node (ref "R14") (pin "2") (pinfunction "2_2") (pintype "passive"))
    )
    (net (code "57") (name "Net-(Q10-PadB)") (class "Default")
      (node (ref "Q10") (pin "B") (pinfunction "B_B") (pintype "passive"))
      (node (ref "R15") (pin "2") (pinfunction "2_2") (pintype "passive"))
    )
    (net (code "58") (name "Net-(Q15-PadB)") (class "Default")
      (node (ref "Q15") (pin "B") (pinfunction "B_B") (pintype "passive"))
      (node (ref "R2") (pin "2") (pinfunction "2_2") (pintype "passive"))
    )
    (net (code "59") (name "Net-(Q16-PadB)") (class "Default")
      (node (ref "Q16") (pin "B") (pinfunction "B_B") (pintype "passive"))
      (node (ref "R3") (pin "2") (pinfunction "2_2") (pintype "passive"))
    )
    (net (code "60") (name "Net-(T2-E)") (class "Default")
      (node (ref "J2") (pin "1") (pinfunction "1_1") (pintype "passive"))
      (node (ref "R4") (pin "1") (pinfunction "1_1") (pintype "passive"))
      (node (ref "T2") (pin "3") (pinfunction "E_3") (pintype "passive"))
    )
    (net (code "61") (name "Net-(U2-REGOUT)") (class "Default")
      (node (ref "C4") (pin "1") (pinfunction "1_1") (pintype "passive"))
      (node (ref "U2") (pin "10") (pinfunction "REGOUT_10") (pintype "bidirectional"))
    )
    (net (code "62") (name "Net-(X4A-S)") (class "Default")
      (node (ref "Q11") (pin "E") (pinfunction "E_E") (pintype "passive"))
      (node (ref "R17") (pin "1") (pinfunction "1_1") (pintype "passive"))
      (node (ref "X4") (pin "1") (pinfunction "S_1") (pintype "passive"))
    )
    (net (code "63") (name "R+12V") (class "Default")
      (node (ref "R25") (pin "2") (pinfunction "2_2") (pintype "passive"))
      (node (ref "R27") (pin "2") (pinfunction "2_2") (pintype "passive"))
      (node (ref "X8") (pin "1") (pinfunction "KL_1") (pintype "passive"))
      (node (ref "X8") (pin "2") (pinfunction "KL_2") (pintype "passive"))
      (node (ref "X8") (pin "5") (pinfunction "KL_5") (pintype "passive"))
      (node (ref "X8") (pin "7") (pinfunction "KL_7") (pintype "passive"))
    )
    (net (code "64") (name "RALI") (class "Default")
      (node (ref "OK4") (pin "8") (pinfunction "COL_8") (pintype "passive"))
      (node (ref "R27") (pin "1") (pinfunction "1_1") (pintype "passive"))
      (node (ref "X8") (pin "6") (pinfunction "KL_6") (pintype "passive"))
    )
    (net (code "65") (name "RBLI") (class "Default")
      (node (ref "OK4") (pin "6") (pinfunction "COL_6") (pintype "passive"))
      (node (ref "R25") (pin "1") (pinfunction "1_1") (pintype "passive"))
      (node (ref "X8") (pin "8") (pinfunction "KL_8") (pintype "passive"))
    )
    (net (code "66") (name "RD+") (class "Default")
      (node (ref "A1") (pin "35") (pinfunction "P$35_35") (pintype "bidirectional"))
      (node (ref "X5") (pin "4") (pinfunction "RD+_4") (pintype "passive"))
    )
    (net (code "67") (name "RD-") (class "Default")
      (node (ref "A1") (pin "36") (pinfunction "P$36_36") (pintype "bidirectional"))
      (node (ref "X5") (pin "6") (pinfunction "RD-_6") (pintype "passive"))
    )
    (net (code "68") (name "RDIR") (class "Default")
      (node (ref "A1") (pin "28") (pinfunction "P$28_28") (pintype "bidirectional"))
      (node (ref "R24") (pin "1") (pinfunction "1_1") (pintype "passive"))
    )
    (net (code "69") (name "REA") (class "Default")
      (node (ref "Q7") (pin "3") (pinfunction "D_3") (pintype "bidirectional"))
      (node (ref "R34") (pin "1") (pinfunction "1_1") (pintype "passive"))
      (node (ref "X2") (pin "3") (pinfunction "S_3") (pintype "passive"))
    )
    (net (code "70") (name "REA3") (class "Default")
      (node (ref "A1") (pin "12") (pinfunction "P$12_12") (pintype "bidirectional"))
      (node (ref "Q7") (pin "2") (pinfunction "S_2") (pintype "bidirectional"))
      (node (ref "R33") (pin "1") (pinfunction "1_1") (pintype "passive"))
    )
    (net (code "71") (name "REB") (class "Default")
      (node (ref "Q9") (pin "3") (pinfunction "D_3") (pintype "bidirectional"))
      (node (ref "R38") (pin "1") (pinfunction "1_1") (pintype "passive"))
      (node (ref "X2") (pin "5") (pinfunction "S_5") (pintype "passive"))
    )
    (net (code "72") (name "REB3") (class "Default")
      (node (ref "A1") (pin "13") (pinfunction "P$13_13") (pintype "bidirectional"))
      (node (ref "Q9") (pin "2") (pinfunction "S_2") (pintype "bidirectional"))
      (node (ref "R35") (pin "1") (pinfunction "1_1") (pintype "passive"))
    )
    (net (code "73") (name "RED") (class "Default")
      (node (ref "A1") (pin "23") (pinfunction "P$23_23") (pintype "bidirectional"))
      (node (ref "R1") (pin "1") (pinfunction "1_1") (pintype "passive"))
    )
    (net (code "74") (name "RED_OUT") (class "Default")
      (node (ref "FQP30N06L") (pin "E") (pinfunction "E_E") (pintype "passive"))
      (node (ref "J1") (pin "3") (pinfunction "3_3") (pintype "passive"))
    )
    (net (code "75") (name "RGND") (class "Default")
      (node (ref "OK4") (pin "5") (pinfunction "EMIT_5") (pintype "passive"))
      (node (ref "OK4") (pin "7") (pinfunction "EMIT_7") (pintype "passive"))
      (node (ref "X8") (pin "10") (pinfunction "KL_10") (pintype "passive"))
      (node (ref "X8") (pin "9") (pinfunction "KL_9") (pintype "passive"))
    )
    (net (code "76") (name "RSPEED") (class "Default")
      (node (ref "A1") (pin "27") (pinfunction "P$27_27") (pintype "bidirectional"))
      (node (ref "R22") (pin "1") (pinfunction "1_1") (pintype "passive"))
    )
    (net (code "77") (name "SAFETY_LIGHT") (class "Default")
      (node (ref "A1") (pin "19") (pinfunction "P$19_19") (pintype "bidirectional"))
      (node (ref "T2") (pin "1") (pinfunction "B_1") (pintype "passive"))
    )
    (net (code "78") (name "SCL") (class "Default")
      (node (ref "A1") (pin "10") (pinfunction "P$10_10") (pintype "bidirectional"))
      (node (ref "R18") (pin "1") (pinfunction "1_1") (pintype "passive"))
      (node (ref "U2") (pin "23") (pinfunction "SCL/SCLK_23") (pintype "bidirectional"))
    )
    (net (code "79") (name "SDA") (class "Default")
      (node (ref "A1") (pin "9") (pinfunction "P$9_9") (pintype "bidirectional"))
      (node (ref "R19") (pin "1") (pinfunction "1_1") (pintype "passive"))
      (node (ref "U2") (pin "24") (pinfunction "SDA/SDI_24") (pintype "bidirectional"))
    )
    (net (code "80") (name "TD+") (class "Default")
      (node (ref "A1") (pin "33") (pinfunction "P$33_33") (pintype "bidirectional"))
      (node (ref "X5") (pin "1") (pinfunction "TD+_1") (pintype "passive"))
    )
    (net (code "81") (name "TD-") (class "Default")
      (node (ref "A1") (pin "34") (pinfunction "P$34_34") (pintype "bidirectional"))
      (node (ref "X5") (pin "3") (pinfunction "TD-_3") (pintype "passive"))
    )
    (net (code "82") (name "unconnected-(A1-P$3-Pad3)") (class "Default")
      (node (ref "A1") (pin "3") (pinfunction "P$3_3") (pintype "bidirectional"))
    )
    (net (code "83") (name "unconnected-(A1-P$4-Pad4)") (class "Default")
      (node (ref "A1") (pin "4") (pinfunction "P$4_4") (pintype "bidirectional"))
    )
    (net (code "84") (name "unconnected-(A1-P$37-Pad37)") (class "Default")
      (node (ref "A1") (pin "37") (pinfunction "P$37_37") (pintype "bidirectional"))
    )
    (net (code "85") (name "unconnected-(A1-P$38-Pad38)") (class "Default")
      (node (ref "A1") (pin "38") (pinfunction "P$38_38") (pintype "bidirectional"))
    )
    (net (code "86") (name "unconnected-(U2-AUX_CL-Pad7)") (class "Default")
      (node (ref "U2") (pin "7") (pinfunction "AUX_CL_7") (pintype "bidirectional"))
    )
    (net (code "87") (name "unconnected-(U2-AUX_DA-Pad21)") (class "Default")
      (node (ref "U2") (pin "21") (pinfunction "AUX_DA_21") (pintype "bidirectional"))
    )
    (net (code "88") (name "unconnected-(X1B-S-Pad2)") (class "Default")
      (node (ref "X1") (pin "2") (pinfunction "S_2") (pintype "passive"))
    )
    (net (code "89") (name "unconnected-(X2B-S-Pad2)") (class "Default")
      (node (ref "X2") (pin "2") (pinfunction "S_2") (pintype "passive"))
    )
    (net (code "90") (name "unconnected-(X5-C_GND-Pad8)") (class "Default")
      (node (ref "X5") (pin "8") (pinfunction "C_GND_8") (pintype "passive"))
    )
    (net (code "91") (name "unconnected-(X5-NC-Pad7)") (class "Default")
      (node (ref "X5") (pin "7") (pinfunction "NC_7") (pintype "passive"))
    )
    (net (code "92") (name "unconnected-(X7D-KL-Pad3)") (class "Default")
      (node (ref "X7") (pin "3") (pinfunction "KL_3") (pintype "passive"))
    )
    (net (code "93") (name "unconnected-(X7E-KL-Pad4)") (class "Default")
      (node (ref "X7") (pin "4") (pinfunction "KL_4") (pintype "passive"))
    )
    (net (code "94") (name "unconnected-(X8D-KL-Pad3)") (class "Default")
      (node (ref "X8") (pin "3") (pinfunction "KL_3") (pintype "passive"))
    )
    (net (code "95") (name "unconnected-(X8E-KL-Pad4)") (class "Default")
      (node (ref "X8") (pin "4") (pinfunction "KL_4") (pintype "passive"))
    )
  )
)
